# Power_Distribution.net
KiCad netlist of a schematic drawn in Altium Designer
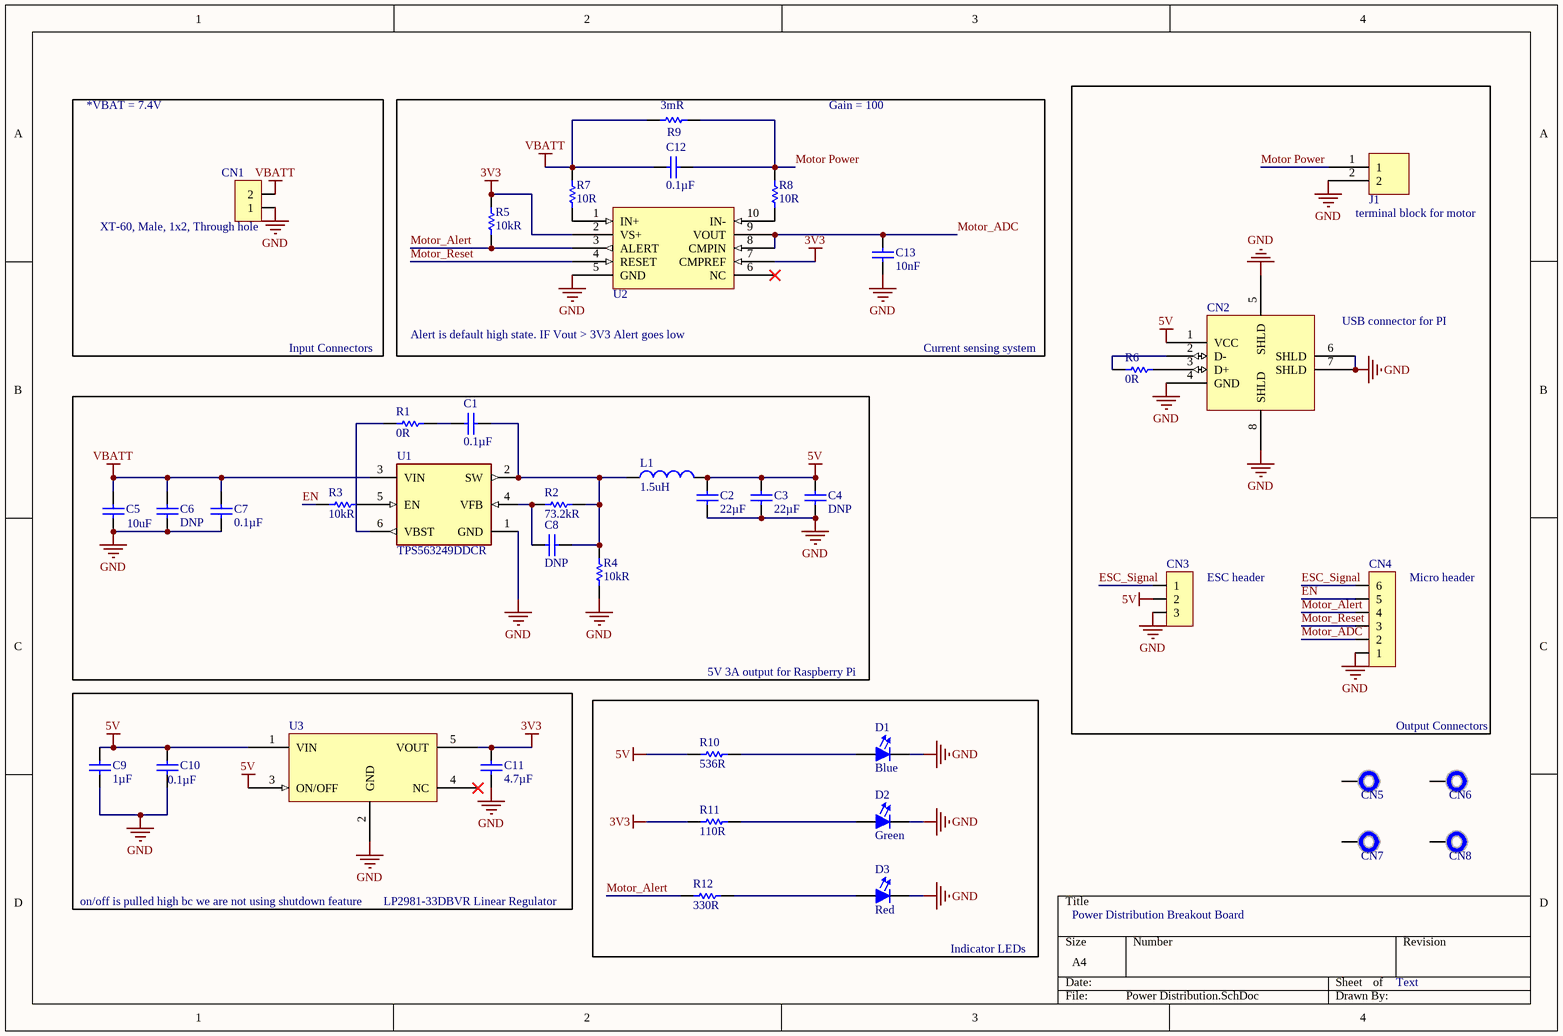
[diagram p0: Power Distribution.SchDoc]

(export (version "E")
  (design (tool "Eeschema 10.0.6"))
  (components
    (comp (ref "C1")
      (value "0.1uF, 50V, 10%, X7R, 0603")
      (footprint "CAPC1608N(0603\")")
      (description "0.1µF ±10% Ceramic Capacitor X7R 0603 (1608 Metric)")
      (fields (field (name "CAPACITANCE") "0.1µF") (field (name "CREATED BY") "Poorna Chander Kalidas"))
      (libsource (lib "") (part "Symbol_1"))
    )
    (comp (ref "C2")
      (value "22µF")
      (footprint "CAPC2012N(0805\")")
      (description "Capacitor, Ceramic, 35V, +/- 20%, 0805 SMD, X5R")
      (fields (field (name "Comment") "22uF 35V 0805 SMD, Ceramic") (field (name "PUBLISHER") "AUVic"))
      (libsource (lib "") (part "Symbol_5"))
    )
    (comp (ref "C3")
      (value "22µF")
      (footprint "CAPC2012N(0805\")")
      (description "Capacitor, Ceramic, 35V, +/- 20%, 0805 SMD, X5R")
      (fields (field (name "Comment") "22uF 35V 0805 SMD, Ceramic") (field (name "PUBLISHER") "AUVic"))
      (libsource (lib "") (part "Symbol_5"))
    )
    (comp (ref "C4")
      (value "DNP")
      (footprint "CAPC1608N(0603\")")
      (description "Placeholder 0603 SMT Footprint")
      (fields
        (field (name "Comment") "Placeholder_Capacitor_0603")
        (field (name "MADE BY") "Ashwin Sira")
        (field (name "PUBLISHER") "AUVic")
      )
      (libsource (lib "AUVIC") (part "Symbol"))
    )
    (comp (ref "C5")
      (value "10uF, 25V, X5R, 0805")
      (footprint "CAPC2013X12N")
      (description "0805 10 uF 25 V ±10% Tolerance X5R SMT Multilayer Ceramic Capacitor")
      (fields (field (name "CAPACITANCE") "10uF") (field (name "TOLERANCE") "10%"))
      (libsource (lib "AUVIC") (part "CAP"))
    )
    (comp (ref "C6")
      (value "DNP")
      (footprint "CAPC3216N(1206\")")
      (description "Placeholder 1206 SMT Footprint")
      (fields
        (field (name "Comment") "Placeholder_Capacitor_1206")
        (field (name "MADE BY") "Ashwin Sira")
        (field (name "PUBLISHER") "AUVic")
      )
      (libsource (lib "AUVIC") (part "Symbol"))
    )
    (comp (ref "C7")
      (value "0.1uF, 50V, 10%, X7R, 0603")
      (footprint "CAPC1608N(0603\")")
      (description "0.1µF ±10% Ceramic Capacitor X7R 0603 (1608 Metric)")
      (fields (field (name "CAPACITANCE") "0.1µF") (field (name "CREATED BY") "Poorna Chander Kalidas"))
      (libsource (lib "") (part "Symbol_1"))
    )
    (comp (ref "C8")
      (value "DNP")
      (footprint "CAPC1608N(0603\")")
      (description "Placeholder 0603 SMT Footprint")
      (fields
        (field (name "Comment") "Placeholder_Capacitor_0603")
        (field (name "MADE BY") "Ashwin Sira")
        (field (name "PUBLISHER") "AUVic")
      )
      (libsource (lib "AUVIC") (part "Symbol"))
    )
    (comp (ref "C9")
      (value "1µF")
      (footprint "CAPC1608N(0603\")")
      (description "Capacitor, Ceramic, 25V, +/- 10%, 0603 SMD, X5R")
      (fields
        (field (name "MFG") "Murata-Electronics-North-America")
        (field (name "Comment") "1uF 25V 0603 SMD, Ceramic")
        (field (name "CREATED BY") "Andy Bates")
        (field (name "PUBLISHER") "AUVic")
      )
      (libsource (lib "") (part "Symbol_1"))
    )
    (comp (ref "C10")
      (value "0.1µF")
      (footprint "CAPC1608N(0603\")")
      (description "Capacitor, Ceramic, 16V, +/- 10%, 0603 SMD, X7R")
      (fields
        (field (name "Comment") "0.1uF 16V 0603 SMD, Ceramic")
        (field (name "CREATED BY") "Andy Bates")
        (field (name "PUBLISHER") "AUVic")
      )
      (libsource (lib "") (part "Symbol_1"))
    )
    (comp (ref "C11")
      (value "4.7µF")
      (footprint "CAPC1608N(0603\")")
      (description "Capacitor, Ceramic, 10V, +/- 10%, 0603 SMD, X5R")
      (fields
        (field (name "MFG") "Samsung")
        (field (name "Comment") "4.7uF 10V 0603 SMD, Ceramic")
        (field (name "CREATED BY") "Ashwin Sira")
        (field (name "PUBLISHER") "AUVic")
      )
      (libsource (lib "") (part "Symbol_1"))
    )
    (comp (ref "C12")
      (value "0.1uF, 50V, 10%, X7R, 0603")
      (footprint "CAPC1608N(0603\")")
      (description "0.1µF ±10% Ceramic Capacitor X7R 0603 (1608 Metric)")
      (fields (field (name "CAPACITANCE") "0.1µF") (field (name "CREATED BY") "Poorna Chander Kalidas"))
      (libsource (lib "") (part "Symbol_1"))
    )
    (comp (ref "C13")
      (value "10nF")
      (footprint "CAPC1608N(0603\")")
      (description "Capacitor, Ceramic, 50V, +/- 10%, 0603 SMD")
      (fields
        (field (name "MFG") "Samsung")
        (field (name "Comment") "10 nF, 50V 0603 SMD, Ceramic")
        (field (name "CREATED BY") "Gabriel")
        (field (name "PUBLISHER") "AUVic")
      )
      (libsource (lib "") (part "Symbol_1"))
    )
    (comp (ref "CN1")
      (value "XT-60, Male, 1x2, Through hole")
      (footprint "XT-60 Male")
      (fields (field (name "PUBLISHER") "Andy Bates"))
      (libsource (lib "") (part "Symbol_6"))
    )
    (comp (ref "CN2")
      (value "USB - Type A Female")
      (footprint "USB - Type A Female-Footprint-1")
      (description "USB - Type A Female USB 2.0 THT")
      (fields (field (name "LCSC PART #") "C168725") (field (name "CREATED BY") "Miguel Manguerra"))
      (libsource (lib "AUVIC") (part "USB - Type A Female"))
    )
    (comp (ref "CN3")
      (value "Header, Male, 1x3, Pitch: 0.1\" (2.54mm), THT")
      (footprint "Header, Male, 1x3, Pitch: 0.1\" (2.54mm),THT")
      (fields
        (field (name "CREATED BY") "Ashwin Sira")
        (field (name "REVIEWED BY") "*")
        (field (name "PUBLISHER") "AUVic")
      )
      (libsource (lib "") (part "Symbol_2"))
    )
    (comp (ref "CN4")
      (value "Header, Male, 1x6")
      (footprint "Header, Male, 1X6")
      (description "1x6, Pads Pitch: 0.1\" (2.54mm), Through hole")
      (libsource (lib "") (part "Symbol_3"))
    )
    (comp (ref "CN5")
      (value "Plated Hole, 1mm")
      (footprint "PLATED_HOLE_1mm")
      (fields
        (field (name "CREATED BY") "Ashwin Sira")
        (field (name "SOURCE") "AUVic_Integrated_Library_Virtual_Components.SchLib")
        (field (name "PUBLISHER") "AUVic")
      )
      (libsource (lib "AUVIC") (part "Plated Hole, 1mm"))
    )
    (comp (ref "CN6")
      (value "Plated Hole, 1mm")
      (footprint "PLATED_HOLE_1mm")
      (fields
        (field (name "CREATED BY") "Ashwin Sira")
        (field (name "SOURCE") "AUVic_Integrated_Library_Virtual_Components.SchLib")
        (field (name "PUBLISHER") "AUVic")
      )
      (libsource (lib "AUVIC") (part "Plated Hole, 1mm"))
    )
    (comp (ref "CN7")
      (value "Plated Hole, 1mm")
      (footprint "PLATED_HOLE_1mm")
      (fields
        (field (name "CREATED BY") "Ashwin Sira")
        (field (name "SOURCE") "AUVic_Integrated_Library_Virtual_Components.SchLib")
        (field (name "PUBLISHER") "AUVic")
      )
      (libsource (lib "AUVIC") (part "Plated Hole, 1mm"))
    )
    (comp (ref "CN8")
      (value "Plated Hole, 1mm")
      (footprint "PLATED_HOLE_1mm")
      (fields
        (field (name "CREATED BY") "Ashwin Sira")
        (field (name "SOURCE") "AUVic_Integrated_Library_Virtual_Components.SchLib")
        (field (name "PUBLISHER") "AUVic")
      )
      (libsource (lib "AUVIC") (part "Plated Hole, 1mm"))
    )
    (comp (ref "D1")
      (value "LBQ39E-N1OO-35-1")
      (footprint "FP-LB_Q39E-MFG")
      (description "LED BLUE DIFFUSED 0603 SMD")
      (fields (field (name "COLOR") "Blue"))
      (libsource (lib "") (part "Symbol_4"))
    )
    (comp (ref "D2")
      (value "LT Q39G-Q1OO-25-1")
      (footprint "FP-LB_Q39E-MFG")
      (description "LED GREEN DIFFUSED 0603 SMD")
      (fields (field (name "COLOR") "Green"))
      (libsource (lib "") (part "Symbol_4"))
    )
    (comp (ref "D3")
      (value "LSQ976-NR-1")
      (footprint "FP-LB_Q39E-MFG")
      (description "LED Red 645nm 2-Pin Chip 0603(1608Metric) T/R")
      (fields (field (name "COLOR") "Red"))
      (libsource (lib "") (part "Symbol_4"))
    )
    (comp (ref "J1")
      (value "2x1 Terminal Block 3.5mm")
      (footprint "2x1 Terminal Block 3.5mm-Footprint-1")
      (description "P=3.5mm Screw terminal RoHS")
      (fields (field (name "LCSC PART #") "C474892") (field (name "CREATED BY") "Miguel Manguerra"))
      (libsource (lib "AUVIC") (part "2x1 Terminal Block 3.5mm"))
    )
    (comp (ref "L1")
      (value "DFE252012P-1R5M=P2")
      (footprint "INDC2520X12N")
      (description "Ind Metal Alloy Shielded 1.5uH 20% 1MHz Powdered Iron 2.6A 1008 T/R")
      (fields (field (name "INDUCTANCE") "1.5uH") (field (name "TOLERANCE") "20%"))
      (libsource (lib "") (part "Symbol_8"))
    )
    (comp (ref "R1")
      (value "0R")
      (footprint "RESC1608N(0603\")")
      (description "0R, 1%, 1/10W, 0603 SMD")
      (fields (field (name "MADE BY") "Ashwin Sira"))
      (libsource (lib "") (part "Symbol_7"))
    )
    (comp (ref "R2")
      (value "ERJ-3EKF7322V")
      (footprint "RESC1608X55X30LL15T15")
      (description "Res Thick Film 0603 73.2K Ohm 1% 0.1W(1/10W) ±100ppm/C Pad SMD Automotive T/R")
      (fields (field (name "TOLERANCE") "1%") (field (name "RESISTANCE") "73.2kR"))
      (libsource (lib "AUVIC") (part "RES"))
    )
    (comp (ref "R3")
      (value "RC0603FR-0710KL")
      (footprint "RESC1608X55X25ML10T15")
      (description "Res General Purpose Thick Film 0603 10K Ohm 1% 1/10W ±100ppm/°C Molded SMD Paper T/R")
      (fields (field (name "RESISTANCE") "10kR") (field (name "TOLERANCE") "1%"))
      (libsource (lib "AUVIC") (part "RES-2"))
    )
    (comp (ref "R4")
      (value "RC0603FR-0710KL")
      (footprint "RESC1608X55X25ML10T15")
      (description "Res General Purpose Thick Film 0603 10K Ohm 1% 1/10W ±100ppm/°C Molded SMD Paper T/R")
      (fields (field (name "RESISTANCE") "10kR") (field (name "TOLERANCE") "1%"))
      (libsource (lib "AUVIC") (part "RES-2"))
    )
    (comp (ref "R5")
      (value "RC0603FR-0710KL")
      (footprint "RESC1608X55X25ML10T15")
      (description "Res General Purpose Thick Film 0603 10K Ohm 1% 1/10W ±100ppm/°C Molded SMD Paper T/R")
      (fields (field (name "RESISTANCE") "10kR") (field (name "TOLERANCE") "1%"))
      (libsource (lib "AUVIC") (part "RES-2"))
    )
    (comp (ref "R6")
      (value "0R")
      (footprint "RESC1608N(0603\")")
      (description "0R, 1%, 1/10W, 0603 SMD")
      (fields (field (name "MADE BY") "Ashwin Sira"))
      (libsource (lib "") (part "Symbol_7"))
    )
    (comp (ref "R7")
      (value "ERJ3EKF10R0V")
      (footprint "FP-ERJ3EK-IPC_A")
      (fields (field (name "RESISTANCE") "10R") (field (name "TOLERANCE") "1%"))
      (libsource (lib "AUVIC") (part "RES"))
    )
    (comp (ref "R8")
      (value "ERJ3EKF10R0V")
      (footprint "FP-ERJ3EK-IPC_A")
      (fields (field (name "RESISTANCE") "10R") (field (name "TOLERANCE") "1%"))
      (libsource (lib "AUVIC") (part "RES"))
    )
    (comp (ref "R9")
      (value "3mR, 1%, 1W, 1206")
      (footprint "RESC1632X07M")
      (description "3 mOhms ±1% 1W Chip Resistor Wide 1206 (3216 Metric), 0612")
      (fields (field (name "RESISTANCE") "3mR"))
      (libsource (lib "AUVIC") (part "3mR"))
    )
    (comp (ref "R10")
      (value "ERJ-3EKF5360V")
      (footprint "RESC1608X55X30NL15T15")
      (description "SMD Chip Resistor, 0603 [1608 Metric], 536 ohm, ERJ3EK Series, 75 V, Thick Film, 100 mW")
      (fields (field (name "TOLERANCE") "1%") (field (name "RESISTANCE") "536R"))
      (libsource (lib "AUVIC") (part "RES"))
    )
    (comp (ref "R11")
      (value "RC0603FR-07110RL")
      (footprint "RESC1608X55X25ML10T15")
      (description "RES SMD 110 OHM 1% 1/10W 0603")
      (fields (field (name "TOLERANCE") "1%") (field (name "RESISTANCE") "110R"))
      (libsource (lib "AUVIC") (part "RES"))
    )
    (comp (ref "R12")
      (value "CRCW0603330RFKEA")
      (footprint "FP-CRCW0603-e3-IPC_C")
      (description "Res Thick Film 0603 330 Ohm 1% 0.1W(1/10W) +/-100ppm/ßC Pad SMD Automotive T/R")
      (fields (field (name "TOLERANCE") "1%") (field (name "RESISTANCE") "330R"))
      (libsource (lib "AUVIC") (part "RES"))
    )
    (comp (ref "U1")
      (value "TPS563249DDCR")
      (footprint "FP-DDC0005A-IPC_B")
      (description "17-V, 3-A, constant 1.4-MHz synchronous step-down voltage regulator 6-SOT-23-THIN -40 to 125")
      (libsource (lib "AUVIC") (part "2eeca152cdac1d6057925bf7033f176"))
    )
    (comp (ref "U2")
      (value "INA381A3IDGSR")
      (footprint "TSSOP50P490X110-10N")
      (description "26V, 350kHz current sense amplifier w/ integrated over-current comparator 10-VSSOP -40 to 125")
      (libsource (lib "AUVIC") (part "INA381A3IDGSR"))
    )
    (comp (ref "U3")
      (value "LP2981-33DBVR")
      (footprint "SOT95P280X145-5N")
      (description "IC REG LINEAR 3.3V 100MA SOT23-5")
      (libsource (lib "AUVIC") (part "LP2981-33DBVR"))
    )
  )
  (nets
    (net (code "1") (name "/EN") (class "Default")
      (node (ref "CN4") (pin "5") (pinfunction "5_5") (pintype "passive"))
      (node (ref "R3") (pin "2") (pinfunction "2_2") (pintype "passive"))
    )
    (net (code "2") (name "/ESC_Signal") (class "Default")
      (node (ref "CN3") (pin "1") (pinfunction "1_1") (pintype "passive"))
      (node (ref "CN4") (pin "6") (pinfunction "6_6") (pintype "passive"))
    )
    (net (code "3") (name "/Motor Power") (class "Default")
      (node (ref "C12") (pin "1") (pinfunction "Anode_1") (pintype "passive"))
      (node (ref "J1") (pin "1") (pinfunction "1_1") (pintype "power_in"))
      (node (ref "R8") (pin "2") (pinfunction "2_2") (pintype "passive"))
      (node (ref "R9") (pin "2") (pinfunction "2_2") (pintype "passive"))
    )
    (net (code "4") (name "/Motor_ADC") (class "Default")
      (node (ref "C13") (pin "2") (pinfunction "Cathode_2") (pintype "passive"))
      (node (ref "CN4") (pin "2") (pinfunction "2_2") (pintype "passive"))
      (node (ref "U2") (pin "8") (pinfunction "CMPIN_8") (pintype "input"))
      (node (ref "U2") (pin "9") (pinfunction "VOUT_9") (pintype "power_in"))
    )
    (net (code "5") (name "/Motor_Alert") (class "Default")
      (node (ref "CN4") (pin "4") (pinfunction "4_4") (pintype "passive"))
      (node (ref "R12") (pin "1") (pinfunction "1_1") (pintype "passive"))
      (node (ref "R5") (pin "1") (pinfunction "1_1") (pintype "passive"))
      (node (ref "U2") (pin "3") (pinfunction "ALERT_3") (pintype "output"))
    )
    (net (code "6") (name "/Motor_Reset") (class "Default")
      (node (ref "CN4") (pin "3") (pinfunction "3_3") (pintype "passive"))
      (node (ref "U2") (pin "4") (pinfunction "RESET_4") (pintype "input"))
    )
    (net (code "7") (name "3V3") (class "Default")
      (node (ref "C11") (pin "2") (pinfunction "Cathode_2") (pintype "passive"))
      (node (ref "R11") (pin "1") (pinfunction "1_1") (pintype "passive"))
      (node (ref "R5") (pin "2") (pinfunction "2_2") (pintype "passive"))
      (node (ref "U2") (pin "2") (pinfunction "VS+_2") (pintype "power_in"))
      (node (ref "U2") (pin "7") (pinfunction "CMPREF_7") (pintype "input"))
      (node (ref "U3") (pin "5") (pinfunction "VOUT_5") (pintype "power_in"))
    )
    (net (code "8") (name "5V") (class "Default")
      (node (ref "C10") (pin "2") (pinfunction "Cathode_2") (pintype "passive"))
      (node (ref "C2") (pin "2") (pinfunction "Cathode_2") (pintype "passive"))
      (node (ref "C3") (pin "2") (pinfunction "Cathode_2") (pintype "passive"))
      (node (ref "C4") (pin "2") (pinfunction "Cathode_2") (pintype "passive"))
      (node (ref "C9") (pin "2") (pinfunction "Cathode_2") (pintype "passive"))
      (node (ref "CN2") (pin "1") (pinfunction "VCC_1") (pintype "power_in"))
      (node (ref "CN3") (pin "2") (pinfunction "2_2") (pintype "passive"))
      (node (ref "L1") (pin "2") (pinfunction "2_2") (pintype "passive"))
      (node (ref "R10") (pin "1") (pinfunction "1_1") (pintype "passive"))
      (node (ref "U3") (pin "1") (pinfunction "VIN_1") (pintype "power_in"))
      (node (ref "U3") (pin "3") (pinfunction "ON/OFF_3") (pintype "input"))
    )
    (net (code "9") (name "GND") (class "Default")
      (node (ref "C10") (pin "1") (pinfunction "Anode_1") (pintype "passive"))
      (node (ref "C11") (pin "1") (pinfunction "Anode_1") (pintype "passive"))
      (node (ref "C13") (pin "1") (pinfunction "Anode_1") (pintype "passive"))
      (node (ref "C2") (pin "1") (pinfunction "Anode_1") (pintype "passive"))
      (node (ref "C3") (pin "1") (pinfunction "Anode_1") (pintype "passive"))
      (node (ref "C4") (pin "1") (pinfunction "Anode_1") (pintype "passive"))
      (node (ref "C5") (pin "2") (pinfunction "2_2") (pintype "passive"))
      (node (ref "C6") (pin "1") (pinfunction "Anode_1") (pintype "passive"))
      (node (ref "C7") (pin "1") (pinfunction "Anode_1") (pintype "passive"))
      (node (ref "C9") (pin "1") (pinfunction "Anode_1") (pintype "passive"))
      (node (ref "CN1") (pin "1") (pinfunction "1_1") (pintype "passive"))
      (node (ref "CN2") (pin "4") (pinfunction "GND_4") (pintype "power_in"))
      (node (ref "CN2") (pin "5") (pinfunction "SHLD_5") (pintype "passive"))
      (node (ref "CN2") (pin "6") (pinfunction "SHLD_6") (pintype "passive"))
      (node (ref "CN2") (pin "7") (pinfunction "SHLD_7") (pintype "passive"))
      (node (ref "CN2") (pin "8") (pinfunction "SHLD_8") (pintype "passive"))
      (node (ref "CN3") (pin "3") (pinfunction "3_3") (pintype "passive"))
      (node (ref "CN4") (pin "1") (pinfunction "1_1") (pintype "passive"))
      (node (ref "D1") (pin "1") (pinfunction "Cathode_1") (pintype "passive"))
      (node (ref "D2") (pin "1") (pinfunction "Cathode_1") (pintype "passive"))
      (node (ref "D3") (pin "1") (pinfunction "Cathode_1") (pintype "passive"))
      (node (ref "J1") (pin "2") (pinfunction "2_2") (pintype "power_in"))
      (node (ref "R4") (pin "1") (pinfunction "1_1") (pintype "passive"))
      (node (ref "U1") (pin "1") (pinfunction "GND_1") (pintype "power_in"))
      (node (ref "U2") (pin "5") (pinfunction "GND_5") (pintype "power_in"))
      (node (ref "U3") (pin "2") (pinfunction "GND_2") (pintype "power_in"))
    )
    (net (code "10") (name "Net-(C1-Anode)") (class "Default")
      (node (ref "C1") (pin "1") (pinfunction "Anode_1") (pintype "passive"))
      (node (ref "C8") (pin "1") (pinfunction "Anode_1") (pintype "passive"))
      (node (ref "L1") (pin "1") (pinfunction "1_1") (pintype "passive"))
      (node (ref "R2") (pin "2") (pinfunction "2_2") (pintype "passive"))
      (node (ref "R4") (pin "2") (pinfunction "2_2") (pintype "passive"))
      (node (ref "U1") (pin "2") (pinfunction "SW_2") (pintype "output"))
    )
    (net (code "11") (name "Net-(C1-Cathode)") (class "Default")
      (node (ref "C1") (pin "2") (pinfunction "Cathode_2") (pintype "passive"))
      (node (ref "R1") (pin "2") (pinfunction "2_2") (pintype "passive"))
    )
    (net (code "12") (name "Net-(C8-Cathode)") (class "Default")
      (node (ref "C8") (pin "2") (pinfunction "Cathode_2") (pintype "passive"))
      (node (ref "R2") (pin "1") (pinfunction "1_1") (pintype "passive"))
      (node (ref "U1") (pin "4") (pinfunction "VFB_4") (pintype "input"))
    )
    (net (code "13") (name "Net-(CN2-D+)") (class "Default")
      (node (ref "CN2") (pin "3") (pinfunction "D+_3") (pintype "bidirectional"))
      (node (ref "R6") (pin "2") (pinfunction "2_2") (pintype "passive"))
    )
    (net (code "14") (name "Net-(CN2-D-)") (class "Default")
      (node (ref "CN2") (pin "2") (pinfunction "D-_2") (pintype "bidirectional"))
      (node (ref "R6") (pin "1") (pinfunction "1_1") (pintype "passive"))
    )
    (net (code "15") (name "Net-(D1-Anode)") (class "Default")
      (node (ref "D1") (pin "2") (pinfunction "Anode_2") (pintype "passive"))
      (node (ref "R10") (pin "2") (pinfunction "2_2") (pintype "passive"))
    )
    (net (code "16") (name "Net-(D2-Anode)") (class "Default")
      (node (ref "D2") (pin "2") (pinfunction "Anode_2") (pintype "passive"))
      (node (ref "R11") (pin "2") (pinfunction "2_2") (pintype "passive"))
    )
    (net (code "17") (name "Net-(D3-Anode)") (class "Default")
      (node (ref "D3") (pin "2") (pinfunction "Anode_2") (pintype "passive"))
      (node (ref "R12") (pin "2") (pinfunction "2_2") (pintype "passive"))
    )
    (net (code "18") (name "Net-(U1-EN)") (class "Default")
      (node (ref "R3") (pin "1") (pinfunction "1_1") (pintype "passive"))
      (node (ref "U1") (pin "5") (pinfunction "EN_5") (pintype "input"))
    )
    (net (code "19") (name "Net-(U1-VBST)") (class "Default")
      (node (ref "R1") (pin "1") (pinfunction "1_1") (pintype "passive"))
      (node (ref "U1") (pin "6") (pinfunction "VBST_6") (pintype "output"))
    )
    (net (code "20") (name "Net-(U2-IN+)") (class "Default")
      (node (ref "R7") (pin "1") (pinfunction "1_1") (pintype "passive"))
      (node (ref "U2") (pin "1") (pinfunction "IN+_1") (pintype "input"))
    )
    (net (code "21") (name "Net-(U2-IN-)") (class "Default")
      (node (ref "R8") (pin "1") (pinfunction "1_1") (pintype "passive"))
      (node (ref "U2") (pin "10") (pinfunction "IN-_10") (pintype "input"))
    )
    (net (code "22") (name "VBATT") (class "Default")
      (node (ref "C12") (pin "2") (pinfunction "Cathode_2") (pintype "passive"))
      (node (ref "C5") (pin "1") (pinfunction "1_1") (pintype "passive"))
      (node (ref "C6") (pin "2") (pinfunction "Cathode_2") (pintype "passive"))
      (node (ref "C7") (pin "2") (pinfunction "Cathode_2") (pintype "passive"))
      (node (ref "CN1") (pin "2") (pinfunction "2_2") (pintype "passive"))
      (node (ref "R7") (pin "2") (pinfunction "2_2") (pintype "passive"))
      (node (ref "R9") (pin "1") (pinfunction "1_1") (pintype "passive"))
      (node (ref "U1") (pin "3") (pinfunction "VIN_3") (pintype "power_in"))
    )
    (net (code "23") (name "unconnected-(CN5-Pad1)") (class "Default")
      (node (ref "CN5") (pin "1") (pinfunction "1_1") (pintype "passive"))
    )
    (net (code "24") (name "unconnected-(CN6-Pad1)") (class "Default")
      (node (ref "CN6") (pin "1") (pinfunction "1_1") (pintype "passive"))
    )
    (net (code "25") (name "unconnected-(CN7-Pad1)") (class "Default")
      (node (ref "CN7") (pin "1") (pinfunction "1_1") (pintype "passive"))
    )
    (net (code "26") (name "unconnected-(CN8-Pad1)") (class "Default")
      (node (ref "CN8") (pin "1") (pinfunction "1_1") (pintype "passive"))
    )
    (net (code "27") (name "unconnected-(U2-NC-Pad6)") (class "Default")
      (node (ref "U2") (pin "6") (pinfunction "NC_6") (pintype "passive+no_connect"))
    )
    (net (code "28") (name "unconnected-(U3-NC-Pad4)") (class "Default")
      (node (ref "U3") (pin "4") (pinfunction "NC_4") (pintype "passive+no_connect"))
    )
  )
)
